# power.net
KiCad netlist of a schematic drawn in Altium Designer
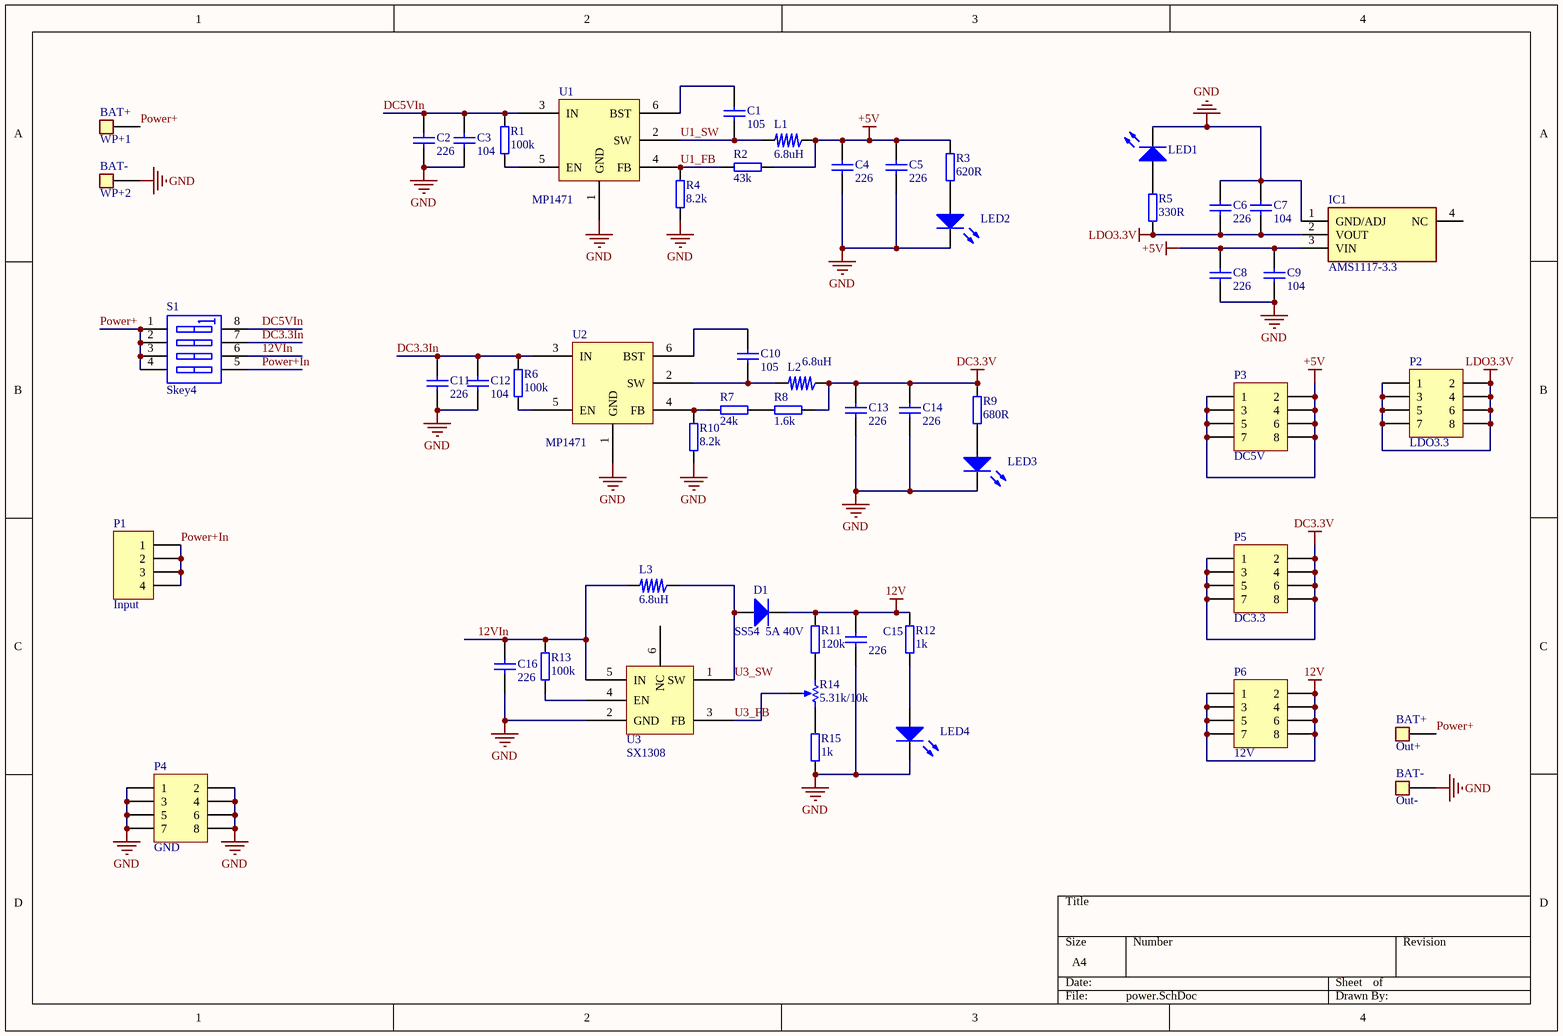
[diagram p0: power.SchDoc]

(export (version "E")
  (design (tool "Eeschema 10.0.6"))
  (components
    (comp (ref "C1")
      (value "105")
      (footprint "CAPC1608[0603]")
      (description "Chip Capacitor, PSpice Model")
      (fields
        (field (name "TOLERANCE") "Y5V")
        (field (name "VOLTAGE") "3V")
        (field (name "PUBLISHER") "Altium Limited")
      )
      (libsource (lib "!)Miscellaneous Integrated Library") (part "Cap Chip 1"))
    )
    (comp (ref "C2")
      (value "226")
      (footprint "CAPC1608[0603]")
      (description "Chip Capacitor, PSpice Model")
      (fields
        (field (name "TOLERANCE") "Y5V")
        (field (name "VOLTAGE") "3V")
        (field (name "PUBLISHER") "Altium Limited")
      )
      (libsource (lib "!)Miscellaneous Integrated Library") (part "Cap Chip 1"))
    )
    (comp (ref "C3")
      (value "104")
      (footprint "CAPC1608[0603]")
      (description "Chip Capacitor, PSpice Model")
      (fields
        (field (name "TOLERANCE") "Y5V")
        (field (name "VOLTAGE") "3V")
        (field (name "PUBLISHER") "Altium Limited")
      )
      (libsource (lib "!)Miscellaneous Integrated Library") (part "Cap Chip 1"))
    )
    (comp (ref "C4")
      (value "226")
      (footprint "CAPC1608[0603]")
      (description "Chip Capacitor, PSpice Model")
      (fields
        (field (name "TOLERANCE") "Y5V")
        (field (name "VOLTAGE") "3V")
        (field (name "PUBLISHER") "Altium Limited")
      )
      (libsource (lib "!)Miscellaneous Integrated Library") (part "Cap Chip 1"))
    )
    (comp (ref "C5")
      (value "226")
      (footprint "CAPC1608[0603]")
      (description "Chip Capacitor, PSpice Model")
      (fields
        (field (name "TOLERANCE") "Y5V")
        (field (name "VOLTAGE") "3V")
        (field (name "PUBLISHER") "Altium Limited")
      )
      (libsource (lib "!)Miscellaneous Integrated Library") (part "Cap Chip 1"))
    )
    (comp (ref "C6")
      (value "226")
      (footprint "CAPC1608[0603]")
      (description "Chip Capacitor, PSpice Model")
      (fields
        (field (name "TOLERANCE") "Y5V")
        (field (name "VOLTAGE") "3V")
        (field (name "PUBLISHER") "Altium Limited")
      )
      (libsource (lib "!)Miscellaneous Integrated Library") (part "Cap Chip 1"))
    )
    (comp (ref "C7")
      (value "104")
      (footprint "CAPC1608[0603]")
      (description "Chip Capacitor, PSpice Model")
      (fields
        (field (name "TOLERANCE") "Y5V")
        (field (name "VOLTAGE") "3V")
        (field (name "PUBLISHER") "Altium Limited")
      )
      (libsource (lib "!)Miscellaneous Integrated Library") (part "Cap Chip 1"))
    )
    (comp (ref "C8")
      (value "226")
      (footprint "CAPC1608[0603]")
      (description "Chip Capacitor, PSpice Model")
      (fields
        (field (name "TOLERANCE") "Y5V")
        (field (name "VOLTAGE") "3V")
        (field (name "PUBLISHER") "Altium Limited")
      )
      (libsource (lib "!)Miscellaneous Integrated Library") (part "Cap Chip 1"))
    )
    (comp (ref "C9")
      (value "104")
      (footprint "CAPC1608[0603]")
      (description "Chip Capacitor, PSpice Model")
      (fields
        (field (name "TOLERANCE") "Y5V")
        (field (name "VOLTAGE") "3V")
        (field (name "PUBLISHER") "Altium Limited")
      )
      (libsource (lib "!)Miscellaneous Integrated Library") (part "Cap Chip 1"))
    )
    (comp (ref "C10")
      (value "105")
      (footprint "CAPC1608[0603]")
      (description "Chip Capacitor, PSpice Model")
      (fields
        (field (name "TOLERANCE") "Y5V")
        (field (name "VOLTAGE") "3V")
        (field (name "PUBLISHER") "Altium Limited")
      )
      (libsource (lib "!)Miscellaneous Integrated Library") (part "Cap Chip 1"))
    )
    (comp (ref "C11")
      (value "226")
      (footprint "CAPC1608[0603]")
      (description "Chip Capacitor, PSpice Model")
      (fields
        (field (name "TOLERANCE") "Y5V")
        (field (name "VOLTAGE") "3V")
        (field (name "PUBLISHER") "Altium Limited")
      )
      (libsource (lib "!)Miscellaneous Integrated Library") (part "Cap Chip 1"))
    )
    (comp (ref "C12")
      (value "104")
      (footprint "CAPC1608[0603]")
      (description "Chip Capacitor, PSpice Model")
      (fields
        (field (name "TOLERANCE") "Y5V")
        (field (name "VOLTAGE") "3V")
        (field (name "PUBLISHER") "Altium Limited")
      )
      (libsource (lib "!)Miscellaneous Integrated Library") (part "Cap Chip 1"))
    )
    (comp (ref "C13")
      (value "226")
      (footprint "CAPC1608[0603]")
      (description "Chip Capacitor, PSpice Model")
      (fields
        (field (name "TOLERANCE") "Y5V")
        (field (name "VOLTAGE") "3V")
        (field (name "PUBLISHER") "Altium Limited")
      )
      (libsource (lib "!)Miscellaneous Integrated Library") (part "Cap Chip 1"))
    )
    (comp (ref "C14")
      (value "226")
      (footprint "CAPC1608[0603]")
      (description "Chip Capacitor, PSpice Model")
      (fields
        (field (name "TOLERANCE") "Y5V")
        (field (name "VOLTAGE") "3V")
        (field (name "PUBLISHER") "Altium Limited")
      )
      (libsource (lib "!)Miscellaneous Integrated Library") (part "Cap Chip 1"))
    )
    (comp (ref "C15")
      (value "226")
      (footprint "CAPC1608[0603]")
      (description "Chip Capacitor, PSpice Model")
      (fields
        (field (name "TOLERANCE") "Y5V")
        (field (name "VOLTAGE") "3V")
        (field (name "PUBLISHER") "Altium Limited")
      )
      (libsource (lib "!)Miscellaneous Integrated Library") (part "Cap Chip 1"))
    )
    (comp (ref "C16")
      (value "226")
      (footprint "CAPC1608[0603]")
      (description "Chip Capacitor, PSpice Model")
      (fields
        (field (name "TOLERANCE") "Y5V")
        (field (name "VOLTAGE") "3V")
        (field (name "PUBLISHER") "Altium Limited")
      )
      (libsource (lib "!)Miscellaneous Integrated Library") (part "Cap Chip 1"))
    )
    (comp (ref "D1")
      (value "SS54  5A 40V")
      (footprint "SMA[DO-214AC]")
      (description "Molded Diode")
      (fields
        (field (name "PARTNUMBER") "SS54  5A 40V")
        (field (name "VOLTAGE") "5A40V")
        (field (name "PUBLISHER") "Altium Limited")
      )
      (libsource (lib "!)Miscellaneous Integrated Library") (part "Diode SMx"))
    )
    (comp (ref "IC1")
      (value "AMS1117-3.3")
      (footprint "SOT229P700X180-4N")
      (description "Integrated Circuit")
      (libsource (lib "SamacSys") (part "AMS1117-3.3"))
    )
    (comp (ref "L1") (value "6.8uH") (footprint "WHC0420") (libsource (lib "BuildDev") (part "L")))
    (comp (ref "L2") (value "6.8uH") (footprint "WHC0420") (libsource (lib "BuildDev") (part "L")))
    (comp (ref "L3") (value "6.8uH") (footprint "WHC0420") (libsource (lib "BuildDev") (part "L")))
    (comp (ref "LED1")
      (value "Red")
      (footprint "LEDC1608(0603)")
      (description "Typical Chip LED")
      (fields (field (name "PUBLISHER") "Altium Limited"))
      (libsource (lib "!)Miscellaneous Integrated Library") (part "LED Chip"))
    )
    (comp (ref "LED2")
      (value "Red")
      (footprint "LEDC1608(0603)")
      (description "Typical Chip LED")
      (fields (field (name "PUBLISHER") "Altium Limited"))
      (libsource (lib "!)Miscellaneous Integrated Library") (part "LED Chip"))
    )
    (comp (ref "LED3")
      (value "Red")
      (footprint "LEDC1608(0603)")
      (description "Typical Chip LED")
      (fields (field (name "PUBLISHER") "Altium Limited"))
      (libsource (lib "!)Miscellaneous Integrated Library") (part "LED Chip"))
    )
    (comp (ref "LED4")
      (value "Red")
      (footprint "LEDC1608(0603)")
      (description "Typical Chip LED")
      (fields (field (name "PUBLISHER") "Altium Limited"))
      (libsource (lib "!)Miscellaneous Integrated Library") (part "LED Chip"))
    )
    (comp (ref "Out+")
      (value "BAT+")
      (footprint "WirePadSingleSide")
      (description "Wire soldering pad.")
      (libsource (lib "!)Miscellaneous Integrated Library") (part "Wire Pad"))
    )
    (comp (ref "Out-")
      (value "BAT-")
      (footprint "WirePadSingleSide")
      (description "Wire soldering pad.")
      (libsource (lib "!)Miscellaneous Integrated Library") (part "Wire Pad"))
    )
    (comp (ref "P1")
      (value "Input")
      (footprint "HDR1X4")
      (description "Header, 4-Pin")
      (fields (field (name "PUBLISHER") "Altium Limited"))
      (libsource (lib "!)Miscellaneous Integrated Library") (part "Header 4"))
    )
    (comp (ref "P2")
      (value "LDO3.3")
      (footprint "HDR2X4")
      (description "Header, 4-Pin, Dual row")
      (fields (field (name "PUBLISHER") "Altium Limited"))
      (libsource (lib "!)Miscellaneous Integrated Library") (part "Header 4X2"))
    )
    (comp (ref "P3")
      (value "DC5V")
      (footprint "HDR2X4")
      (description "Header, 4-Pin, Dual row")
      (fields (field (name "PUBLISHER") "Altium Limited"))
      (libsource (lib "!)Miscellaneous Integrated Library") (part "Header 4X2"))
    )
    (comp (ref "P4")
      (value "GND")
      (footprint "HDR2X4")
      (description "Header, 4-Pin, Dual row")
      (fields (field (name "PUBLISHER") "Altium Limited"))
      (libsource (lib "!)Miscellaneous Integrated Library") (part "Header 4X2"))
    )
    (comp (ref "P5")
      (value "DC3.3")
      (footprint "HDR2X4")
      (description "Header, 4-Pin, Dual row")
      (fields (field (name "PUBLISHER") "Altium Limited"))
      (libsource (lib "!)Miscellaneous Integrated Library") (part "Header 4X2"))
    )
    (comp (ref "P6")
      (value "12V")
      (footprint "HDR2X4")
      (description "Header, 4-Pin, Dual row")
      (fields (field (name "PUBLISHER") "Altium Limited"))
      (libsource (lib "!)Miscellaneous Integrated Library") (part "Header 4X2"))
    )
    (comp (ref "R1")
      (value "100k")
      (footprint "RESC1608[0603]")
      (description "Chip Resistor, PSpice Model, IPC PCB Library Drawing")
      (fields (field (name "TOLERANCE") "5%") (field (name "PUBLISHER") "Altium Limited"))
      (libsource (lib "!)Miscellaneous Integrated Library") (part "Res Chip 2p 1"))
    )
    (comp (ref "R2")
      (value "43k")
      (footprint "RESC1608[0603]")
      (description "Chip Resistor, PSpice Model, IPC PCB Library Drawing")
      (fields (field (name "TOLERANCE") "5%") (field (name "PUBLISHER") "Altium Limited"))
      (libsource (lib "!)Miscellaneous Integrated Library") (part "Res Chip 2p 1"))
    )
    (comp (ref "R3")
      (value "620R")
      (footprint "RESC1608[0603]")
      (description "Chip Resistor, PSpice Model, IPC PCB Library Drawing")
      (fields (field (name "TOLERANCE") "5%") (field (name "PUBLISHER") "Altium Limited"))
      (libsource (lib "!)Miscellaneous Integrated Library") (part "Res Chip 2p 1"))
    )
    (comp (ref "R4")
      (value "8.2k")
      (footprint "RESC1608[0603]")
      (description "Chip Resistor, PSpice Model, IPC PCB Library Drawing")
      (fields (field (name "TOLERANCE") "5%") (field (name "PUBLISHER") "Altium Limited"))
      (libsource (lib "!)Miscellaneous Integrated Library") (part "Res Chip 2p 1"))
    )
    (comp (ref "R5")
      (value "330R")
      (footprint "RESC1608[0603]")
      (description "Chip Resistor, PSpice Model, IPC PCB Library Drawing")
      (fields (field (name "TOLERANCE") "5%") (field (name "PUBLISHER") "Altium Limited"))
      (libsource (lib "!)Miscellaneous Integrated Library") (part "Res Chip 2p 1"))
    )
    (comp (ref "R6")
      (value "100k")
      (footprint "RESC1608[0603]")
      (description "Chip Resistor, PSpice Model, IPC PCB Library Drawing")
      (fields (field (name "TOLERANCE") "5%") (field (name "PUBLISHER") "Altium Limited"))
      (libsource (lib "!)Miscellaneous Integrated Library") (part "Res Chip 2p 1"))
    )
    (comp (ref "R7")
      (value "24k")
      (footprint "RESC1608[0603]")
      (description "Chip Resistor, PSpice Model, IPC PCB Library Drawing")
      (fields (field (name "TOLERANCE") "5%") (field (name "PUBLISHER") "Altium Limited"))
      (libsource (lib "!)Miscellaneous Integrated Library") (part "Res Chip 2p 1"))
    )
    (comp (ref "R8")
      (value "1.6k")
      (footprint "RESC1608[0603]")
      (description "Chip Resistor, PSpice Model, IPC PCB Library Drawing")
      (fields (field (name "TOLERANCE") "5%") (field (name "PUBLISHER") "Altium Limited"))
      (libsource (lib "!)Miscellaneous Integrated Library") (part "Res Chip 2p 1"))
    )
    (comp (ref "R9")
      (value "680R")
      (footprint "RESC1608[0603]")
      (description "Chip Resistor, PSpice Model, IPC PCB Library Drawing")
      (fields (field (name "TOLERANCE") "5%") (field (name "PUBLISHER") "Altium Limited"))
      (libsource (lib "!)Miscellaneous Integrated Library") (part "Res Chip 2p 1"))
    )
    (comp (ref "R10")
      (value "8.2k")
      (footprint "RESC1608[0603]")
      (description "Chip Resistor, PSpice Model, IPC PCB Library Drawing")
      (fields (field (name "TOLERANCE") "5%") (field (name "PUBLISHER") "Altium Limited"))
      (libsource (lib "!)Miscellaneous Integrated Library") (part "Res Chip 2p 1"))
    )
    (comp (ref "R11")
      (value "120k")
      (footprint "RESC1608[0603]")
      (description "Chip Resistor, PSpice Model, IPC PCB Library Drawing")
      (fields (field (name "TOLERANCE") "5%") (field (name "PUBLISHER") "Altium Limited"))
      (libsource (lib "!)Miscellaneous Integrated Library") (part "Res Chip 2p 1"))
    )
    (comp (ref "R12")
      (value "1k")
      (footprint "RESC1608[0603]")
      (description "Chip Resistor, PSpice Model, IPC PCB Library Drawing")
      (fields (field (name "TOLERANCE") "5%") (field (name "PUBLISHER") "Altium Limited"))
      (libsource (lib "!)Miscellaneous Integrated Library") (part "Res Chip 2p 1"))
    )
    (comp (ref "R13")
      (value "100k")
      (footprint "RESC1608[0603]")
      (description "Chip Resistor, PSpice Model, IPC PCB Library Drawing")
      (fields (field (name "TOLERANCE") "5%") (field (name "PUBLISHER") "Altium Limited"))
      (libsource (lib "!)Miscellaneous Integrated Library") (part "Res Chip 2p 1"))
    )
    (comp (ref "R14")
      (value "5.31k/10k")
      (footprint "Rhostat2")
      (libsource (lib "BuildDev") (part "Rhostat"))
    )
    (comp (ref "R15")
      (value "1k")
      (footprint "RESC1608[0603]")
      (description "Chip Resistor, PSpice Model, IPC PCB Library Drawing")
      (fields (field (name "TOLERANCE") "5%") (field (name "PUBLISHER") "Altium Limited"))
      (libsource (lib "!)Miscellaneous Integrated Library") (part "Res Chip 2p 1"))
    )
    (comp (ref "S1") (value "Skey4") (footprint "Skey4") (libsource (lib "BuildDev") (part "Skey4")))
    (comp (ref "U1")
      (value "MP1471")
      (footprint "TSOT23-6")
      (description "4.7v-16V Input\r\n16V3A\r\n500K")
      (libsource (lib "BuildDev") (part "MP1471"))
    )
    (comp (ref "U2")
      (value "MP1471")
      (footprint "TSOT23-6")
      (description "4.7v-16V Input\r\n16V3A\r\n500K")
      (libsource (lib "BuildDev") (part "MP1471"))
    )
    (comp (ref "U3")
      (value "SX1308")
      (footprint "SOT23-6")
      (description "boost\r\n1.2MHz\r\n2V-24V input\r\nup to 28V Output")
      (libsource (lib "BuildDev") (part "SX1308"))
    )
    (comp (ref "WP+1")
      (value "BAT+")
      (footprint "WirePadSingleSide")
      (description "Wire soldering pad.")
      (libsource (lib "!)Miscellaneous Integrated Library") (part "Wire Pad"))
    )
    (comp (ref "WP+2")
      (value "BAT-")
      (footprint "WirePadSingleSide")
      (description "Wire soldering pad.")
      (libsource (lib "!)Miscellaneous Integrated Library") (part "Wire Pad"))
    )
  )
  (nets
    (net (code "1") (name "+5V") (class "Default")
      (node (ref "C4") (pin "1") (pinfunction "1_1") (pintype "passive"))
      (node (ref "C5") (pin "1") (pinfunction "1_1") (pintype "passive"))
      (node (ref "C8") (pin "1") (pinfunction "1_1") (pintype "passive"))
      (node (ref "C9") (pin "1") (pinfunction "1_1") (pintype "passive"))
      (node (ref "IC1") (pin "3") (pinfunction "VIN_3") (pintype "passive"))
      (node (ref "L1") (pin "1") (pinfunction "1_1") (pintype "passive"))
      (node (ref "P3") (pin "1") (pinfunction "1_1") (pintype "passive"))
      (node (ref "P3") (pin "2") (pinfunction "2_2") (pintype "passive"))
      (node (ref "P3") (pin "3") (pinfunction "3_3") (pintype "passive"))
      (node (ref "P3") (pin "4") (pinfunction "4_4") (pintype "passive"))
      (node (ref "P3") (pin "5") (pinfunction "5_5") (pintype "passive"))
      (node (ref "P3") (pin "6") (pinfunction "6_6") (pintype "passive"))
      (node (ref "P3") (pin "7") (pinfunction "7_7") (pintype "passive"))
      (node (ref "P3") (pin "8") (pinfunction "8_8") (pintype "passive"))
      (node (ref "R2") (pin "2") (pinfunction "2_2") (pintype "passive"))
      (node (ref "R3") (pin "2") (pinfunction "2_2") (pintype "passive"))
    )
    (net (code "2") (name "/12VIn") (class "Default")
      (node (ref "C16") (pin "1") (pinfunction "1_1") (pintype "passive"))
      (node (ref "L3") (pin "2") (pinfunction "2_2") (pintype "passive"))
      (node (ref "R13") (pin "1") (pinfunction "1_1") (pintype "passive"))
      (node (ref "S1") (pin "6") (pinfunction "B3_6") (pintype "passive"))
      (node (ref "U3") (pin "5") (pinfunction "IN_5") (pintype "passive"))
    )
    (net (code "3") (name "/DC3.3In") (class "Default")
      (node (ref "C11") (pin "1") (pinfunction "1_1") (pintype "passive"))
      (node (ref "C12") (pin "1") (pinfunction "1_1") (pintype "passive"))
      (node (ref "R6") (pin "1") (pinfunction "1_1") (pintype "passive"))
      (node (ref "S1") (pin "7") (pinfunction "B2_7") (pintype "passive"))
      (node (ref "U2") (pin "3") (pinfunction "IN_3") (pintype "passive"))
    )
    (net (code "4") (name "/DC5VIn") (class "Default")
      (node (ref "C2") (pin "1") (pinfunction "1_1") (pintype "passive"))
      (node (ref "C3") (pin "1") (pinfunction "1_1") (pintype "passive"))
      (node (ref "R1") (pin "1") (pinfunction "1_1") (pintype "passive"))
      (node (ref "S1") (pin "8") (pinfunction "B1_8") (pintype "passive"))
      (node (ref "U1") (pin "3") (pinfunction "IN_3") (pintype "passive"))
    )
    (net (code "5") (name "/Power+") (class "Default")
      (node (ref "Out+") (pin "1") (pinfunction "0_1") (pintype "passive"))
      (node (ref "S1") (pin "1") (pinfunction "A1_1") (pintype "passive"))
      (node (ref "S1") (pin "2") (pinfunction "A2_2") (pintype "passive"))
      (node (ref "S1") (pin "3") (pinfunction "A3_3") (pintype "passive"))
      (node (ref "S1") (pin "4") (pinfunction "A4_4") (pintype "passive"))
      (node (ref "WP+1") (pin "1") (pinfunction "0_1") (pintype "passive"))
    )
    (net (code "6") (name "/Power+In") (class "Default")
      (node (ref "P1") (pin "1") (pinfunction "1_1") (pintype "passive"))
      (node (ref "P1") (pin "2") (pinfunction "2_2") (pintype "passive"))
      (node (ref "P1") (pin "3") (pinfunction "3_3") (pintype "passive"))
      (node (ref "P1") (pin "4") (pinfunction "4_4") (pintype "passive"))
      (node (ref "S1") (pin "5") (pinfunction "B4_5") (pintype "passive"))
    )
    (net (code "7") (name "/U1_FB") (class "Default")
      (node (ref "R2") (pin "1") (pinfunction "1_1") (pintype "passive"))
      (node (ref "R4") (pin "1") (pinfunction "1_1") (pintype "passive"))
      (node (ref "U1") (pin "4") (pinfunction "FB_4") (pintype "passive"))
    )
    (net (code "8") (name "/U1_SW") (class "Default")
      (node (ref "C1") (pin "2") (pinfunction "2_2") (pintype "passive"))
      (node (ref "L1") (pin "2") (pinfunction "2_2") (pintype "passive"))
      (node (ref "U1") (pin "2") (pinfunction "SW_2") (pintype "passive"))
    )
    (net (code "9") (name "/U3_FB") (class "Default")
      (node (ref "R14") (pin "3") (pinfunction "TAP_3") (pintype "passive"))
      (node (ref "U3") (pin "3") (pinfunction "FB_3") (pintype "passive"))
    )
    (net (code "10") (name "/U3_SW") (class "Default")
      (node (ref "D1") (pin "A") (pinfunction "A_A") (pintype "passive"))
      (node (ref "L3") (pin "1") (pinfunction "1_1") (pintype "passive"))
      (node (ref "U3") (pin "1") (pinfunction "SW_1") (pintype "passive"))
    )
    (net (code "11") (name "12V") (class "Default")
      (node (ref "C15") (pin "1") (pinfunction "1_1") (pintype "passive"))
      (node (ref "D1") (pin "K") (pinfunction "K_K") (pintype "passive"))
      (node (ref "P6") (pin "1") (pinfunction "1_1") (pintype "passive"))
      (node (ref "P6") (pin "2") (pinfunction "2_2") (pintype "passive"))
      (node (ref "P6") (pin "3") (pinfunction "3_3") (pintype "passive"))
      (node (ref "P6") (pin "4") (pinfunction "4_4") (pintype "passive"))
      (node (ref "P6") (pin "5") (pinfunction "5_5") (pintype "passive"))
      (node (ref "P6") (pin "6") (pinfunction "6_6") (pintype "passive"))
      (node (ref "P6") (pin "7") (pinfunction "7_7") (pintype "passive"))
      (node (ref "P6") (pin "8") (pinfunction "8_8") (pintype "passive"))
      (node (ref "R11") (pin "2") (pinfunction "2_2") (pintype "passive"))
      (node (ref "R12") (pin "2") (pinfunction "2_2") (pintype "passive"))
    )
    (net (code "12") (name "DC3.3V") (class "Default")
      (node (ref "C13") (pin "1") (pinfunction "1_1") (pintype "passive"))
      (node (ref "C14") (pin "1") (pinfunction "1_1") (pintype "passive"))
      (node (ref "L2") (pin "1") (pinfunction "1_1") (pintype "passive"))
      (node (ref "P5") (pin "1") (pinfunction "1_1") (pintype "passive"))
      (node (ref "P5") (pin "2") (pinfunction "2_2") (pintype "passive"))
      (node (ref "P5") (pin "3") (pinfunction "3_3") (pintype "passive"))
      (node (ref "P5") (pin "4") (pinfunction "4_4") (pintype "passive"))
      (node (ref "P5") (pin "5") (pinfunction "5_5") (pintype "passive"))
      (node (ref "P5") (pin "6") (pinfunction "6_6") (pintype "passive"))
      (node (ref "P5") (pin "7") (pinfunction "7_7") (pintype "passive"))
      (node (ref "P5") (pin "8") (pinfunction "8_8") (pintype "passive"))
      (node (ref "R8") (pin "2") (pinfunction "2_2") (pintype "passive"))
      (node (ref "R9") (pin "2") (pinfunction "2_2") (pintype "passive"))
    )
    (net (code "13") (name "GND") (class "Default")
      (node (ref "C11") (pin "2") (pinfunction "2_2") (pintype "passive"))
      (node (ref "C12") (pin "2") (pinfunction "2_2") (pintype "passive"))
      (node (ref "C13") (pin "2") (pinfunction "2_2") (pintype "passive"))
      (node (ref "C14") (pin "2") (pinfunction "2_2") (pintype "passive"))
      (node (ref "C15") (pin "2") (pinfunction "2_2") (pintype "passive"))
      (node (ref "C16") (pin "2") (pinfunction "2_2") (pintype "passive"))
      (node (ref "C2") (pin "2") (pinfunction "2_2") (pintype "passive"))
      (node (ref "C3") (pin "2") (pinfunction "2_2") (pintype "passive"))
      (node (ref "C4") (pin "2") (pinfunction "2_2") (pintype "passive"))
      (node (ref "C5") (pin "2") (pinfunction "2_2") (pintype "passive"))
      (node (ref "C6") (pin "1") (pinfunction "1_1") (pintype "passive"))
      (node (ref "C7") (pin "1") (pinfunction "1_1") (pintype "passive"))
      (node (ref "C8") (pin "2") (pinfunction "2_2") (pintype "passive"))
      (node (ref "C9") (pin "2") (pinfunction "2_2") (pintype "passive"))
      (node (ref "IC1") (pin "1") (pinfunction "GND/ADJ_1") (pintype "passive"))
      (node (ref "LED1") (pin "C") (pinfunction "C_C") (pintype "passive"))
      (node (ref "LED2") (pin "C") (pinfunction "C_C") (pintype "passive"))
      (node (ref "LED3") (pin "C") (pinfunction "C_C") (pintype "passive"))
      (node (ref "LED4") (pin "C") (pinfunction "C_C") (pintype "passive"))
      (node (ref "Out-") (pin "1") (pinfunction "0_1") (pintype "passive"))
      (node (ref "P4") (pin "1") (pinfunction "1_1") (pintype "passive"))
      (node (ref "P4") (pin "2") (pinfunction "2_2") (pintype "passive"))
      (node (ref "P4") (pin "3") (pinfunction "3_3") (pintype "passive"))
      (node (ref "P4") (pin "4") (pinfunction "4_4") (pintype "passive"))
      (node (ref "P4") (pin "5") (pinfunction "5_5") (pintype "passive"))
      (node (ref "P4") (pin "6") (pinfunction "6_6") (pintype "passive"))
      (node (ref "P4") (pin "7") (pinfunction "7_7") (pintype "passive"))
      (node (ref "P4") (pin "8") (pinfunction "8_8") (pintype "passive"))
      (node (ref "R10") (pin "2") (pinfunction "2_2") (pintype "passive"))
      (node (ref "R15") (pin "1") (pinfunction "1_1") (pintype "passive"))
      (node (ref "R4") (pin "2") (pinfunction "2_2") (pintype "passive"))
      (node (ref "U1") (pin "1") (pinfunction "GND_1") (pintype "passive"))
      (node (ref "U2") (pin "1") (pinfunction "GND_1") (pintype "passive"))
      (node (ref "U3") (pin "2") (pinfunction "GND_2") (pintype "passive"))
      (node (ref "WP+2") (pin "1") (pinfunction "0_1") (pintype "passive"))
    )
    (net (code "14") (name "LDO3.3V") (class "Default")
      (node (ref "C6") (pin "2") (pinfunction "2_2") (pintype "passive"))
      (node (ref "C7") (pin "2") (pinfunction "2_2") (pintype "passive"))
      (node (ref "IC1") (pin "2") (pinfunction "VOUT_2") (pintype "passive"))
      (node (ref "P2") (pin "1") (pinfunction "1_1") (pintype "passive"))
      (node (ref "P2") (pin "2") (pinfunction "2_2") (pintype "passive"))
      (node (ref "P2") (pin "3") (pinfunction "3_3") (pintype "passive"))
      (node (ref "P2") (pin "4") (pinfunction "4_4") (pintype "passive"))
      (node (ref "P2") (pin "5") (pinfunction "5_5") (pintype "passive"))
      (node (ref "P2") (pin "6") (pinfunction "6_6") (pintype "passive"))
      (node (ref "P2") (pin "7") (pinfunction "7_7") (pintype "passive"))
      (node (ref "P2") (pin "8") (pinfunction "8_8") (pintype "passive"))
      (node (ref "R5") (pin "1") (pinfunction "1_1") (pintype "passive"))
    )
    (net (code "15") (name "Net-(LED1-PadA)") (class "Default")
      (node (ref "LED1") (pin "A") (pinfunction "A_A") (pintype "passive"))
      (node (ref "R5") (pin "2") (pinfunction "2_2") (pintype "passive"))
    )
    (net (code "16") (name "Net-(LED2-PadA)") (class "Default")
      (node (ref "LED2") (pin "A") (pinfunction "A_A") (pintype "passive"))
      (node (ref "R3") (pin "1") (pinfunction "1_1") (pintype "passive"))
    )
    (net (code "17") (name "Net-(LED3-PadA)") (class "Default")
      (node (ref "LED3") (pin "A") (pinfunction "A_A") (pintype "passive"))
      (node (ref "R9") (pin "1") (pinfunction "1_1") (pintype "passive"))
    )
    (net (code "18") (name "Net-(LED4-PadA)") (class "Default")
      (node (ref "LED4") (pin "A") (pinfunction "A_A") (pintype "passive"))
      (node (ref "R12") (pin "1") (pinfunction "1_1") (pintype "passive"))
    )
    (net (code "19") (name "Net-(R7-Pad2)") (class "Default")
      (node (ref "R7") (pin "2") (pinfunction "2_2") (pintype "passive"))
      (node (ref "R8") (pin "1") (pinfunction "1_1") (pintype "passive"))
    )
    (net (code "20") (name "Net-(R14-BOT)") (class "Default")
      (node (ref "R14") (pin "2") (pinfunction "BOT_2") (pintype "passive"))
      (node (ref "R15") (pin "2") (pinfunction "2_2") (pintype "passive"))
    )
    (net (code "21") (name "Net-(R14-TOP)") (class "Default")
      (node (ref "R11") (pin "1") (pinfunction "1_1") (pintype "passive"))
      (node (ref "R14") (pin "1") (pinfunction "TOP_1") (pintype "passive"))
    )
    (net (code "22") (name "Net-(U1-BST)") (class "Default")
      (node (ref "C1") (pin "1") (pinfunction "1_1") (pintype "passive"))
      (node (ref "U1") (pin "6") (pinfunction "BST_6") (pintype "passive"))
    )
    (net (code "23") (name "Net-(U1-EN)") (class "Default")
      (node (ref "R1") (pin "2") (pinfunction "2_2") (pintype "passive"))
      (node (ref "U1") (pin "5") (pinfunction "EN_5") (pintype "passive"))
    )
    (net (code "24") (name "Net-(U2-BST)") (class "Default")
      (node (ref "C10") (pin "1") (pinfunction "1_1") (pintype "passive"))
      (node (ref "U2") (pin "6") (pinfunction "BST_6") (pintype "passive"))
    )
    (net (code "25") (name "Net-(U2-EN)") (class "Default")
      (node (ref "R6") (pin "2") (pinfunction "2_2") (pintype "passive"))
      (node (ref "U2") (pin "5") (pinfunction "EN_5") (pintype "passive"))
    )
    (net (code "26") (name "Net-(U2-FB)") (class "Default")
      (node (ref "R10") (pin "1") (pinfunction "1_1") (pintype "passive"))
      (node (ref "R7") (pin "1") (pinfunction "1_1") (pintype "passive"))
      (node (ref "U2") (pin "4") (pinfunction "FB_4") (pintype "passive"))
    )
    (net (code "27") (name "Net-(U2-SW)") (class "Default")
      (node (ref "C10") (pin "2") (pinfunction "2_2") (pintype "passive"))
      (node (ref "L2") (pin "2") (pinfunction "2_2") (pintype "passive"))
      (node (ref "U2") (pin "2") (pinfunction "SW_2") (pintype "passive"))
    )
    (net (code "28") (name "Net-(U3-EN)") (class "Default")
      (node (ref "R13") (pin "2") (pinfunction "2_2") (pintype "passive"))
      (node (ref "U3") (pin "4") (pinfunction "EN_4") (pintype "passive"))
    )
    (net (code "29") (name "unconnected-(IC1-NC-Pad4)") (class "Default")
      (node (ref "IC1") (pin "4") (pinfunction "NC_4") (pintype "passive"))
    )
    (net (code "30") (name "unconnected-(U3-NC-Pad6)") (class "Default")
      (node (ref "U3") (pin "6") (pinfunction "NC_6") (pintype "passive"))
    )
  )
)
